# MainBoard_MCU.net
KiCad netlist of a schematic drawn in Altium Designer
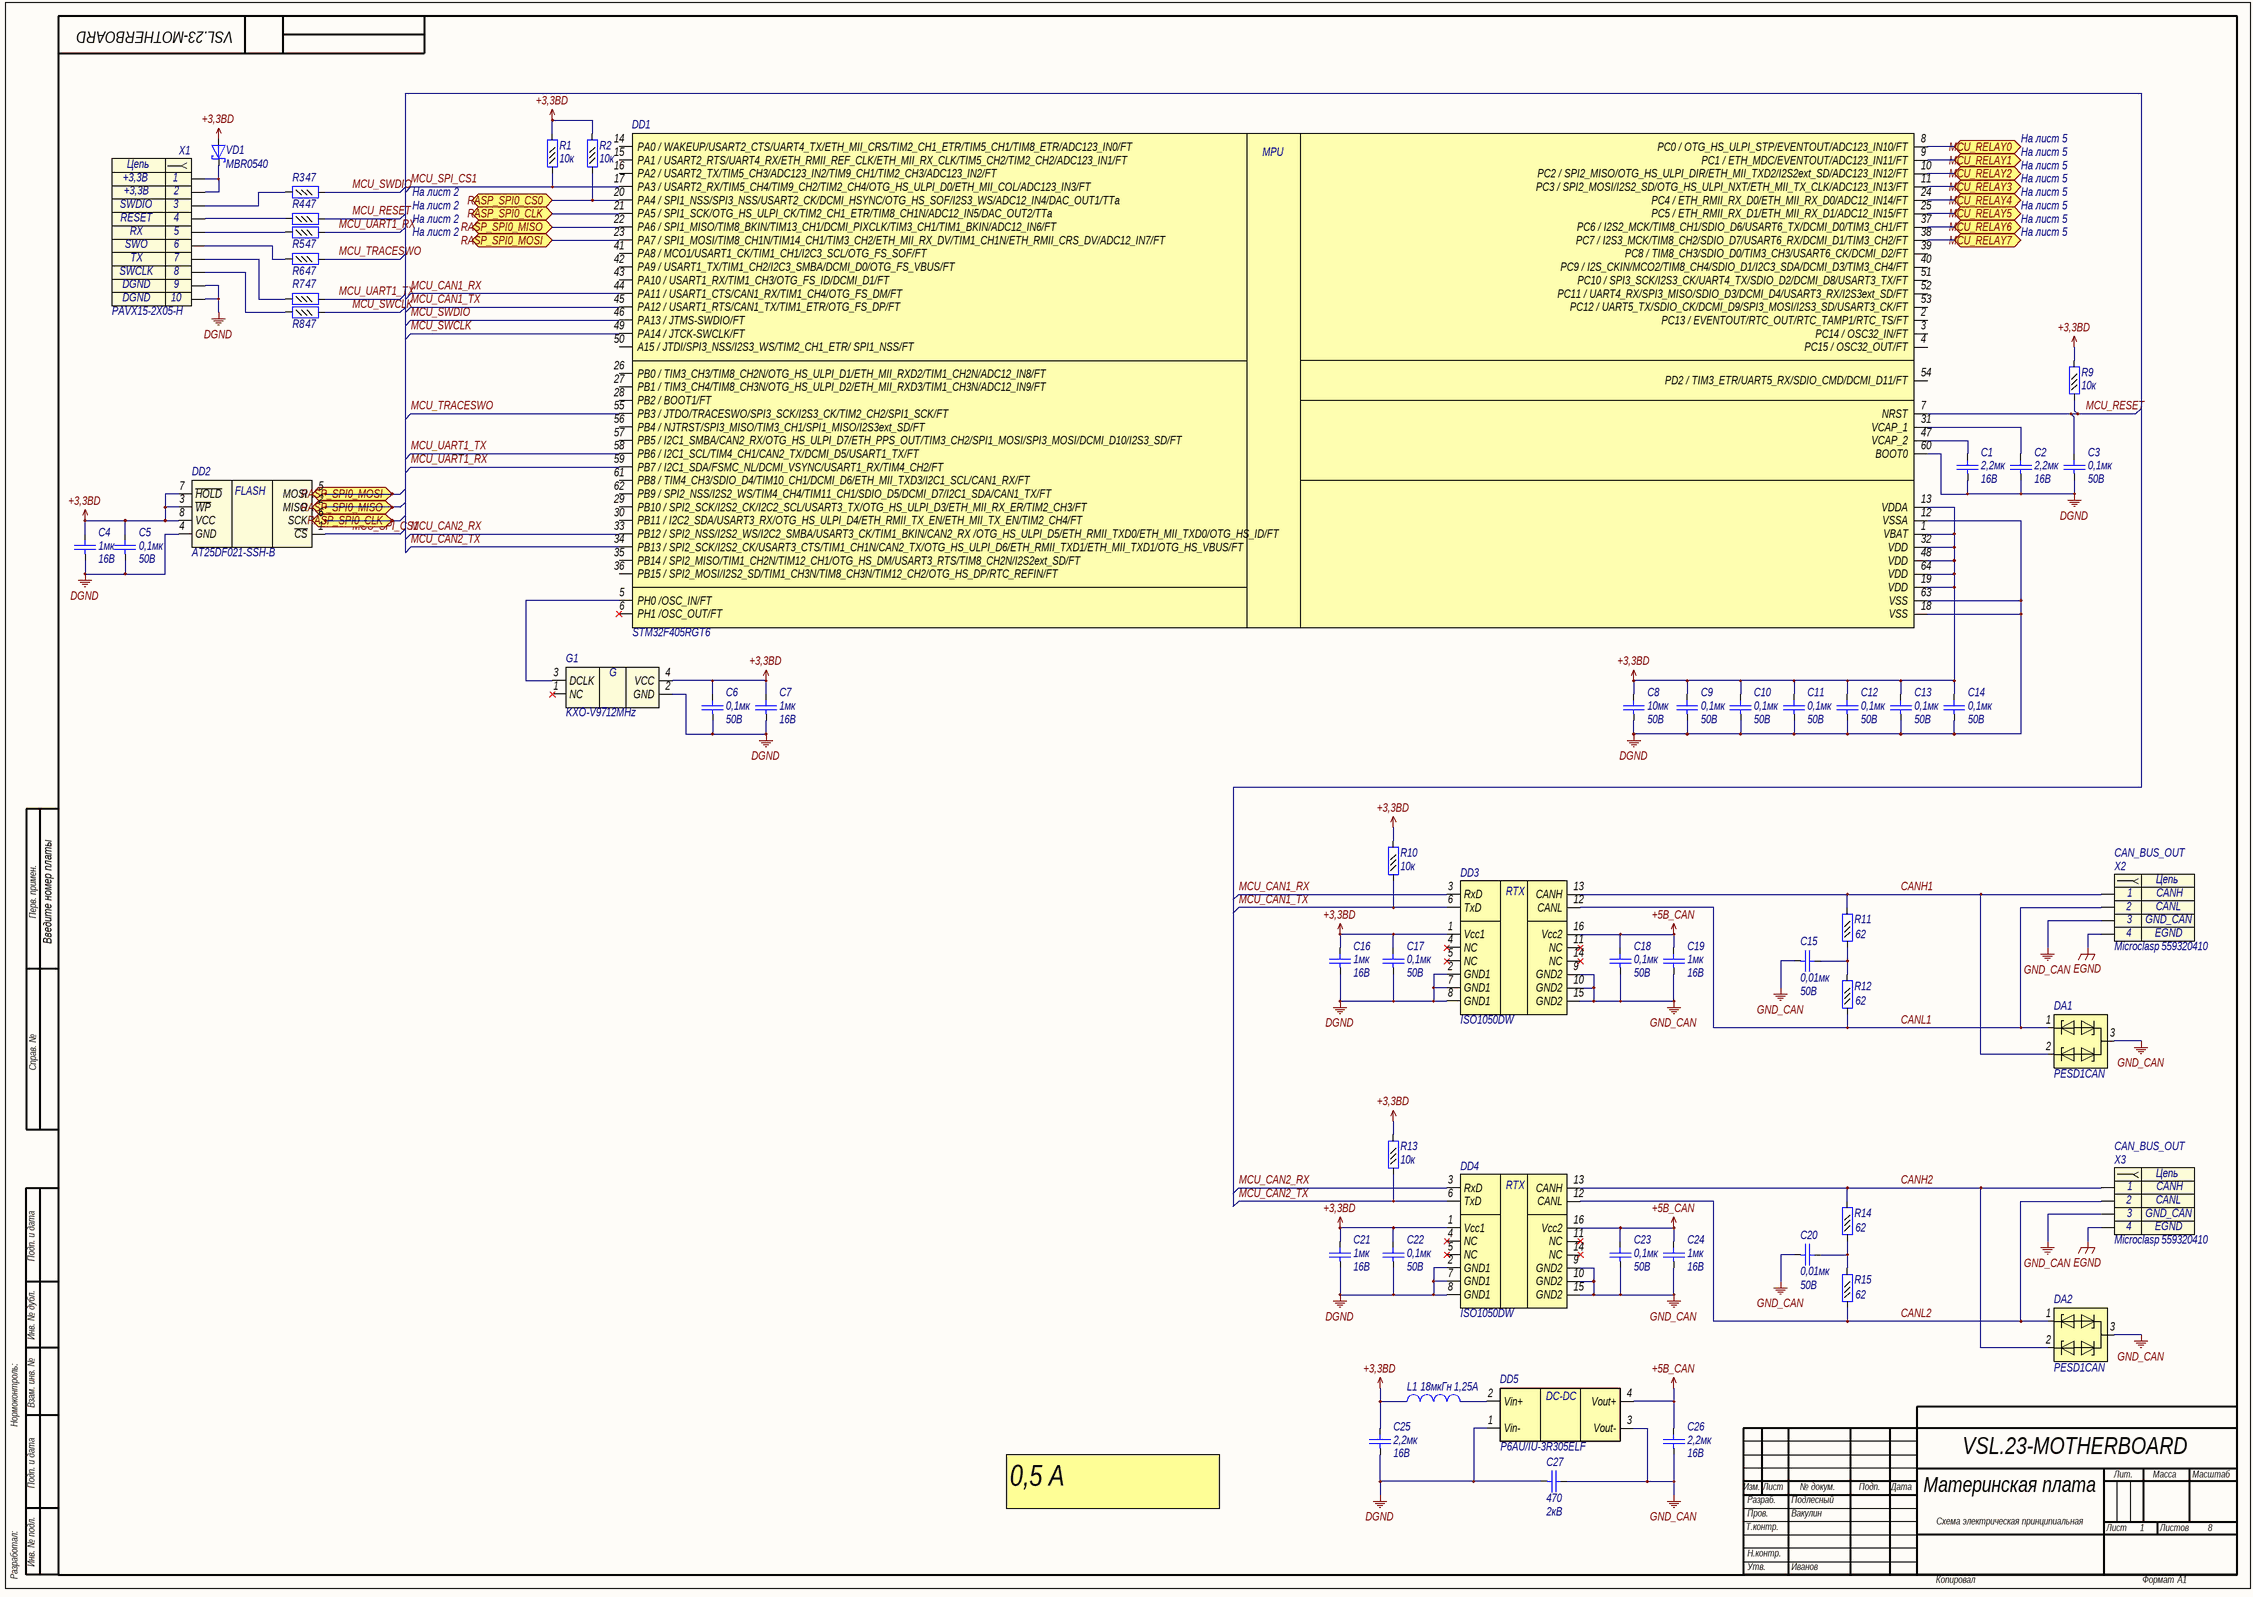
[diagram p0: MainBoard_MCU.SchDoc]

(export (version "E")
  (design (tool "Eeschema 10.0.6"))
  (components
    (comp (ref "C1")
      (value "2,2мк")
      (footprint "C0603")
      (description "Конденсатор")
      (fields (field (name "VOLTAGE") "16B") (field (name "PART NUMBER") "GRM188Z71C225ME43J"))
      (libsource (lib "MOP44") (part "Capacitor"))
    )
    (comp (ref "C2")
      (value "2,2мк")
      (footprint "C0603")
      (description "Конденсатор")
      (fields (field (name "VOLTAGE") "16B") (field (name "PART NUMBER") "GRM188Z71C225ME43J"))
      (libsource (lib "MOP44") (part "Capacitor"))
    )
    (comp (ref "C3")
      (value "0,1мк")
      (footprint "C0402")
      (description "Конденсатор")
      (fields
        (field (name "VOLTAGE") "50В")
        (field (name "PART NUMBER") "GRM155R71H104KE14D ")
        (field (name "Comment") "Capacitor")
      )
      (libsource (lib "MOP44") (part "Capacitor"))
    )
    (comp (ref "C4")
      (value "1мк")
      (footprint "C0603")
      (description "Конденсатор")
      (fields
        (field (name "VOLTAGE") "16B")
        (field (name "PART NUMBER") "GRM188R71C105KA12D**")
        (field (name "Comment") "Capacitor")
      )
      (libsource (lib "MOP44") (part "Capacitor"))
    )
    (comp (ref "C5")
      (value "0,1мк")
      (footprint "C0402")
      (description "Конденсатор")
      (fields
        (field (name "VOLTAGE") "50В")
        (field (name "PART NUMBER") "GRM155R71H104KE14D ")
        (field (name "Comment") "Capacitor")
      )
      (libsource (lib "MOP44") (part "Capacitor"))
    )
    (comp (ref "C6")
      (value "0,1мк")
      (footprint "C0402")
      (description "Конденсатор")
      (fields
        (field (name "VOLTAGE") "50В")
        (field (name "PART NUMBER") "GRM155R71H104KE14D ")
        (field (name "Comment") "Capacitor")
      )
      (libsource (lib "MOP44") (part "Capacitor"))
    )
    (comp (ref "C7")
      (value "1мк")
      (footprint "C0603")
      (description "Конденсатор")
      (fields
        (field (name "VOLTAGE") "16B")
        (field (name "PART NUMBER") "GRM188R71C105KA12D**")
        (field (name "Comment") "Capacitor")
      )
      (libsource (lib "MOP44") (part "Capacitor"))
    )
    (comp (ref "C8")
      (value "10мк")
      (footprint "C1210")
      (description "Конденсатор")
      (fields (field (name "VOLTAGE") "50В") (field (name "PART NUMBER") "C3225X7R1H106K250AC"))
      (libsource (lib "MOP44") (part "Capacitor"))
    )
    (comp (ref "C9")
      (value "0,1мк")
      (footprint "C0402")
      (description "Конденсатор")
      (fields
        (field (name "VOLTAGE") "50В")
        (field (name "PART NUMBER") "GRM155R71H104KE14D ")
        (field (name "Comment") "Capacitor")
      )
      (libsource (lib "MOP44") (part "Capacitor"))
    )
    (comp (ref "C10")
      (value "0,1мк")
      (footprint "C0402")
      (description "Конденсатор")
      (fields
        (field (name "VOLTAGE") "50В")
        (field (name "PART NUMBER") "GRM155R71H104KE14D ")
        (field (name "Comment") "Capacitor")
      )
      (libsource (lib "MOP44") (part "Capacitor"))
    )
    (comp (ref "C11")
      (value "0,1мк")
      (footprint "C0402")
      (description "Конденсатор")
      (fields
        (field (name "VOLTAGE") "50В")
        (field (name "PART NUMBER") "GRM155R71H104KE14D ")
        (field (name "Comment") "Capacitor")
      )
      (libsource (lib "MOP44") (part "Capacitor"))
    )
    (comp (ref "C12")
      (value "0,1мк")
      (footprint "C0402")
      (description "Конденсатор")
      (fields
        (field (name "VOLTAGE") "50В")
        (field (name "PART NUMBER") "GRM155R71H104KE14D ")
        (field (name "Comment") "Capacitor")
      )
      (libsource (lib "MOP44") (part "Capacitor"))
    )
    (comp (ref "C13")
      (value "0,1мк")
      (footprint "C0402")
      (description "Конденсатор")
      (fields
        (field (name "VOLTAGE") "50В")
        (field (name "PART NUMBER") "GRM155R71H104KE14D ")
        (field (name "Comment") "Capacitor")
      )
      (libsource (lib "MOP44") (part "Capacitor"))
    )
    (comp (ref "C14")
      (value "0,1мк")
      (footprint "C0402")
      (description "Конденсатор")
      (fields
        (field (name "VOLTAGE") "50В")
        (field (name "PART NUMBER") "GRM155R71H104KE14D ")
        (field (name "Comment") "Capacitor")
      )
      (libsource (lib "MOP44") (part "Capacitor"))
    )
    (comp (ref "C15")
      (value "0,01мк")
      (footprint "C0402")
      (description "Конденсатор")
      (fields
        (field (name "VOLTAGE") "50B")
        (field (name "PART NUMBER") "GRM155R71H103K")
        (field (name "Comment") "Capacitor")
      )
      (libsource (lib "MOP44") (part "Capacitor"))
    )
    (comp (ref "C16")
      (value "1мк")
      (footprint "C0603")
      (description "Конденсатор")
      (fields
        (field (name "VOLTAGE") "16B")
        (field (name "PART NUMBER") "GRM188R71C105KA12D**")
        (field (name "Comment") "Capacitor")
      )
      (libsource (lib "MOP44") (part "Capacitor"))
    )
    (comp (ref "C17")
      (value "0,1мк")
      (footprint "C0402")
      (description "Конденсатор")
      (fields
        (field (name "VOLTAGE") "50В")
        (field (name "PART NUMBER") "GRM155R71H104KE14D ")
        (field (name "Comment") "Capacitor")
      )
      (libsource (lib "MOP44") (part "Capacitor"))
    )
    (comp (ref "C18")
      (value "0,1мк")
      (footprint "C0402")
      (description "Конденсатор")
      (fields
        (field (name "VOLTAGE") "50В")
        (field (name "PART NUMBER") "GRM155R71H104KE14D ")
        (field (name "Comment") "Capacitor")
      )
      (libsource (lib "MOP44") (part "Capacitor"))
    )
    (comp (ref "C19")
      (value "1мк")
      (footprint "C0603")
      (description "Конденсатор")
      (fields
        (field (name "VOLTAGE") "16B")
        (field (name "PART NUMBER") "GRM188R71C105KA12D**")
        (field (name "Comment") "Capacitor")
      )
      (libsource (lib "MOP44") (part "Capacitor"))
    )
    (comp (ref "C20")
      (value "0,01мк")
      (footprint "C0402")
      (description "Конденсатор")
      (fields
        (field (name "VOLTAGE") "50B")
        (field (name "PART NUMBER") "GRM155R71H103K")
        (field (name "Comment") "Capacitor")
      )
      (libsource (lib "MOP44") (part "Capacitor"))
    )
    (comp (ref "C21")
      (value "1мк")
      (footprint "C0603")
      (description "Конденсатор")
      (fields
        (field (name "VOLTAGE") "16B")
        (field (name "PART NUMBER") "GRM188R71C105KA12D**")
        (field (name "Comment") "Capacitor")
      )
      (libsource (lib "MOP44") (part "Capacitor"))
    )
    (comp (ref "C22")
      (value "0,1мк")
      (footprint "C0402")
      (description "Конденсатор")
      (fields
        (field (name "VOLTAGE") "50В")
        (field (name "PART NUMBER") "GRM155R71H104KE14D ")
        (field (name "Comment") "Capacitor")
      )
      (libsource (lib "MOP44") (part "Capacitor"))
    )
    (comp (ref "C23")
      (value "0,1мк")
      (footprint "C0402")
      (description "Конденсатор")
      (fields
        (field (name "VOLTAGE") "50В")
        (field (name "PART NUMBER") "GRM155R71H104KE14D ")
        (field (name "Comment") "Capacitor")
      )
      (libsource (lib "MOP44") (part "Capacitor"))
    )
    (comp (ref "C24")
      (value "1мк")
      (footprint "C0603")
      (description "Конденсатор")
      (fields
        (field (name "VOLTAGE") "16B")
        (field (name "PART NUMBER") "GRM188R71C105KA12D**")
        (field (name "Comment") "Capacitor")
      )
      (libsource (lib "MOP44") (part "Capacitor"))
    )
    (comp (ref "C25")
      (value "2,2мк")
      (footprint "C0603")
      (description "Конденсатор")
      (fields (field (name "VOLTAGE") "16B") (field (name "PART NUMBER") "GRM188Z71C225ME43J"))
      (libsource (lib "MOP44") (part "Capacitor"))
    )
    (comp (ref "C26")
      (value "2,2мк")
      (footprint "C0603")
      (description "Конденсатор")
      (fields (field (name "VOLTAGE") "16B") (field (name "PART NUMBER") "GRM188Z71C225ME43J"))
      (libsource (lib "MOP44") (part "Capacitor"))
    )
    (comp (ref "C27")
      (value "470")
      (footprint "C1206")
      (description "Конденсатор")
      (fields
        (field (name "VOLTAGE") "2кВ")
        (field (name "PART NUMBER") "CC1206KKX7RDBB471 ")
        (field (name "Comment") "Capacitor")
      )
      (libsource (lib "MOP44") (part "Capacitor"))
    )
    (comp (ref "DA1")
      (value "PESD")
      (footprint "SOT23-3")
      (description "TVS")
      (fields (field (name "PART NUMBER") "PESD1CAN"))
      (libsource (lib "MOP44") (part "PESD"))
    )
    (comp (ref "DA2")
      (value "PESD")
      (footprint "SOT23-3")
      (description "TVS")
      (fields (field (name "PART NUMBER") "PESD1CAN"))
      (libsource (lib "MOP44") (part "PESD"))
    )
    (comp (ref "DD1")
      (value "STM32F405RGT6")
      (footprint "LQFP64")
      (libsource (lib "MOP44") (part "STM32F405RGT6"))
    )
    (comp (ref "DD2")
      (value "AT25DF021")
      (footprint "SO8")
      (description "SPI Serial Flash  Memory")
      (fields (field (name "MANUFACTURER") "Adesto") (field (name "PART NUMBER") "AT25DF021-SSH-B"))
      (libsource (lib "MOP44") (part "AT25DF021"))
    )
    (comp (ref "DD3")
      (value "~")
      (footprint "SO16")
      (description "Isolated CAN Transceiver")
      (fields (field (name "PART NUMBER") "ISO1050DW"))
      (libsource (lib "MOP44") (part "ISO1050DW"))
    )
    (comp (ref "DD4")
      (value "~")
      (footprint "SO16")
      (description "Isolated CAN Transceiver")
      (fields (field (name "PART NUMBER") "ISO1050DW"))
      (libsource (lib "MOP44") (part "ISO1050DW"))
    )
    (comp (ref "DD5")
      (value "P6AU-xxxxELF")
      (footprint "SIP4")
      (description "DC/DC преобразователь")
      (fields
        (field (name "PART NUMBER") "P6AU/IU-3R305ELF")
        (field (name "MANUFACTURER") "PEAK Electronics")
      )
      (libsource (lib "MOP44") (part "P6AU-xxxxELF"))
    )
    (comp (ref "G1")
      (value "KXO")
      (footprint "QSMD7x5.2x1.8")
      (description "Кварц. генер. 32.768 МГц (HCMOS/TTL)")
      (fields (field (name "FREQUENCE") "12MHz") (field (name "PART NUMBER") "KXO-V97"))
      (libsource (lib "MOP44") (part "KXO"))
    )
    (comp (ref "L1")
      (value "18мкГн")
      (footprint "SDR0604")
      (description "EMI Suppression Filter")
      (fields
        (field (name "RATED CURRENT") "1,25A")
        (field (name "PART NUMBER") "SDR0604- 180YL")
        (field (name "Comment") "Inductor")
      )
      (libsource (lib "MOP44") (part "Inductor"))
    )
    (comp (ref "R1")
      (value "10к")
      (footprint "R0402")
      (description "Резистор")
      (fields (field (name "PART NUMBER") "RC0402FR-0710KL") (field (name "POWER") "0,062Вт"))
      (libsource (lib "") (part "Resistor_0,062Вт_1"))
    )
    (comp (ref "R2")
      (value "10к")
      (footprint "R0402")
      (description "Резистор")
      (fields (field (name "PART NUMBER") "RC0402FR-0710KL") (field (name "POWER") "0,062Вт"))
      (libsource (lib "") (part "Resistor_0,062Вт_1"))
    )
    (comp (ref "R3")
      (value "47")
      (footprint "R0402")
      (description "Резистор")
      (fields (field (name "PART NUMBER") "RC0402FR-0747RL") (field (name "POWER") "0,062Вт"))
      (libsource (lib "MOP44") (part "Resistor_0,062Вт"))
    )
    (comp (ref "R4")
      (value "47")
      (footprint "R0402")
      (description "Резистор")
      (fields (field (name "PART NUMBER") "RC0402FR-0747RL") (field (name "POWER") "0,062Вт"))
      (libsource (lib "MOP44") (part "Resistor_0,062Вт"))
    )
    (comp (ref "R5")
      (value "47")
      (footprint "R0402")
      (description "Резистор")
      (fields (field (name "PART NUMBER") "RC0402FR-0747RL") (field (name "POWER") "0,062Вт"))
      (libsource (lib "MOP44") (part "Resistor_0,062Вт"))
    )
    (comp (ref "R6")
      (value "47")
      (footprint "R0402")
      (description "Резистор")
      (fields (field (name "PART NUMBER") "RC0402FR-0747RL") (field (name "POWER") "0,062Вт"))
      (libsource (lib "MOP44") (part "Resistor_0,062Вт"))
    )
    (comp (ref "R7")
      (value "47")
      (footprint "R0402")
      (description "Резистор")
      (fields (field (name "PART NUMBER") "RC0402FR-0747RL") (field (name "POWER") "0,062Вт"))
      (libsource (lib "MOP44") (part "Resistor_0,062Вт"))
    )
    (comp (ref "R8")
      (value "47")
      (footprint "R0402")
      (description "Резистор")
      (fields (field (name "PART NUMBER") "RC0402FR-0747RL") (field (name "POWER") "0,062Вт"))
      (libsource (lib "MOP44") (part "Resistor_0,062Вт"))
    )
    (comp (ref "R9")
      (value "10к")
      (footprint "R0402")
      (description "Резистор")
      (fields (field (name "PART NUMBER") "RC0402FR-0710KL") (field (name "POWER") "0,062Вт"))
      (libsource (lib "") (part "Resistor_0,062Вт_1"))
    )
    (comp (ref "R10")
      (value "10к")
      (footprint "R0402")
      (description "Резистор")
      (fields (field (name "PART NUMBER") "RC0402FR-0710KL") (field (name "POWER") "0,062Вт"))
      (libsource (lib "") (part "Resistor_0,062Вт_1"))
    )
    (comp (ref "R11")
      (value "62")
      (footprint "R0402")
      (description "Резистор")
      (fields (field (name "PART NUMBER") "RC0402FR-0762RL") (field (name "POWER") "0,062Вт"))
      (libsource (lib "") (part "Resistor_0,062Вт_1"))
    )
    (comp (ref "R12")
      (value "62")
      (footprint "R0402")
      (description "Резистор")
      (fields (field (name "PART NUMBER") "RC0402FR-0762RL") (field (name "POWER") "0,062Вт"))
      (libsource (lib "") (part "Resistor_0,062Вт_1"))
    )
    (comp (ref "R13")
      (value "10к")
      (footprint "R0402")
      (description "Резистор")
      (fields (field (name "PART NUMBER") "RC0402FR-0710KL") (field (name "POWER") "0,062Вт"))
      (libsource (lib "") (part "Resistor_0,062Вт_1"))
    )
    (comp (ref "R14")
      (value "62")
      (footprint "R0402")
      (description "Резистор")
      (fields (field (name "PART NUMBER") "RC0402FR-0762RL") (field (name "POWER") "0,062Вт"))
      (libsource (lib "") (part "Resistor_0,062Вт_1"))
    )
    (comp (ref "R15")
      (value "62")
      (footprint "R0402")
      (description "Резистор")
      (fields (field (name "PART NUMBER") "RC0402FR-0762RL") (field (name "POWER") "0,062Вт"))
      (libsource (lib "") (part "Resistor_0,062Вт_1"))
    )
    (comp (ref "VD1")
      (value "DiodeSchottky")
      (footprint "SOD-123")
      (description "Диод Шоттки")
      (fields (field (name "PART NUMBER") "MBR0540"))
      (libsource (lib "MOP44") (part "DiodeSchottky"))
    )
    (comp (ref "X1")
      (value "Header_10_sct")
      (footprint "PAVX15-2X05-H")
      (description "Разъем - 10 конт. розетка")
      (fields (field (name "PART NUMBER") "PAVX15-2X05-H"))
      (libsource (lib "MOP44") (part "Header_10_sct"))
    )
    (comp (ref "X2")
      (value "CAN_BUS_OUT")
      (footprint "MOLEX_559320410")
      (description "Разъем - 4 конт. розетка")
      (fields (field (name "PART NUMBER") "559320410"))
      (libsource (lib "MOP44") (part "Header_4_sct"))
    )
    (comp (ref "X3")
      (value "CAN_BUS_OUT")
      (footprint "MOLEX_559320410")
      (description "Разъем - 4 конт. розетка")
      (fields (field (name "PART NUMBER") "559320410"))
      (libsource (lib "MOP44") (part "Header_4_sct"))
    )
  )
  (nets
    (net (code "1") (name "+3,3BD") (class "Default")
      (node (ref "C10") (pin "2") (pinfunction "2_2") (pintype "passive"))
      (node (ref "C11") (pin "2") (pinfunction "2_2") (pintype "passive"))
      (node (ref "C12") (pin "2") (pinfunction "2_2") (pintype "passive"))
      (node (ref "C13") (pin "2") (pinfunction "2_2") (pintype "passive"))
      (node (ref "C14") (pin "2") (pinfunction "2_2") (pintype "passive"))
      (node (ref "C16") (pin "2") (pinfunction "2_2") (pintype "passive"))
      (node (ref "C17") (pin "2") (pinfunction "2_2") (pintype "passive"))
      (node (ref "C21") (pin "2") (pinfunction "2_2") (pintype "passive"))
      (node (ref "C22") (pin "2") (pinfunction "2_2") (pintype "passive"))
      (node (ref "C25") (pin "2") (pinfunction "2_2") (pintype "passive"))
      (node (ref "C4") (pin "2") (pinfunction "2_2") (pintype "passive"))
      (node (ref "C5") (pin "2") (pinfunction "2_2") (pintype "passive"))
      (node (ref "C6") (pin "2") (pinfunction "2_2") (pintype "passive"))
      (node (ref "C7") (pin "2") (pinfunction "2_2") (pintype "passive"))
      (node (ref "C8") (pin "2") (pinfunction "2_2") (pintype "passive"))
      (node (ref "C9") (pin "2") (pinfunction "2_2") (pintype "passive"))
      (node (ref "DD1") (pin "1") (pinfunction "VBAT_1") (pintype "passive"))
      (node (ref "DD1") (pin "13") (pinfunction "VDDA_13") (pintype "passive"))
      (node (ref "DD1") (pin "19") (pinfunction "VDD_19") (pintype "passive"))
      (node (ref "DD1") (pin "32") (pinfunction "VDD_32") (pintype "passive"))
      (node (ref "DD1") (pin "48") (pinfunction "VDD_48") (pintype "passive"))
      (node (ref "DD1") (pin "64") (pinfunction "VDD_64") (pintype "passive"))
      (node (ref "DD2") (pin "3") (pinfunction "~{WP}_3") (pintype "power_in"))
      (node (ref "DD2") (pin "7") (pinfunction "~{HOLD}_7") (pintype "power_in"))
      (node (ref "DD2") (pin "8") (pinfunction "VCC_8") (pintype "power_in"))
      (node (ref "DD3") (pin "1") (pinfunction "Vcc1_1") (pintype "passive"))
      (node (ref "DD4") (pin "1") (pinfunction "Vcc1_1") (pintype "passive"))
      (node (ref "G1") (pin "4") (pinfunction "VCC_4") (pintype "power_in"))
      (node (ref "L1") (pin "1") (pinfunction "1_1") (pintype "passive"))
      (node (ref "R1") (pin "2") (pinfunction "2_2") (pintype "passive"))
      (node (ref "R10") (pin "2") (pinfunction "2_2") (pintype "passive"))
      (node (ref "R13") (pin "2") (pinfunction "2_2") (pintype "passive"))
      (node (ref "R2") (pin "2") (pinfunction "2_2") (pintype "passive"))
      (node (ref "R9") (pin "2") (pinfunction "2_2") (pintype "passive"))
      (node (ref "VD1") (pin "2") (pinfunction "A_2") (pintype "passive"))
    )
    (net (code "2") (name "+5B_CAN") (class "Default")
      (node (ref "C18") (pin "2") (pinfunction "2_2") (pintype "passive"))
      (node (ref "C19") (pin "2") (pinfunction "2_2") (pintype "passive"))
      (node (ref "C23") (pin "2") (pinfunction "2_2") (pintype "passive"))
      (node (ref "C24") (pin "2") (pinfunction "2_2") (pintype "passive"))
      (node (ref "C26") (pin "2") (pinfunction "2_2") (pintype "passive"))
      (node (ref "DD3") (pin "16") (pinfunction "Vcc2_16") (pintype "passive"))
      (node (ref "DD4") (pin "16") (pinfunction "Vcc2_16") (pintype "passive"))
      (node (ref "DD5") (pin "4") (pinfunction "Vout+_4") (pintype "passive"))
    )
    (net (code "3") (name "/CANH1") (class "Default")
      (node (ref "DA1") (pin "2") (pinfunction "1_2") (pintype "passive"))
      (node (ref "DD3") (pin "13") (pinfunction "CANH_13") (pintype "passive"))
      (node (ref "R11") (pin "2") (pinfunction "2_2") (pintype "passive"))
      (node (ref "X2") (pin "1") (pinfunction "1_1") (pintype "passive"))
    )
    (net (code "4") (name "/CANH2") (class "Default")
      (node (ref "DA2") (pin "2") (pinfunction "1_2") (pintype "passive"))
      (node (ref "DD4") (pin "13") (pinfunction "CANH_13") (pintype "passive"))
      (node (ref "R14") (pin "2") (pinfunction "2_2") (pintype "passive"))
      (node (ref "X3") (pin "1") (pinfunction "1_1") (pintype "passive"))
    )
    (net (code "5") (name "/CANL1") (class "Default")
      (node (ref "DA1") (pin "1") (pintype "passive"))
      (node (ref "DD3") (pin "12") (pinfunction "CANL_12") (pintype "passive"))
      (node (ref "R12") (pin "1") (pinfunction "1_1") (pintype "passive"))
      (node (ref "X2") (pin "2") (pinfunction "2_2") (pintype "passive"))
    )
    (net (code "6") (name "/CANL2") (class "Default")
      (node (ref "DA2") (pin "1") (pintype "passive"))
      (node (ref "DD4") (pin "12") (pinfunction "CANL_12") (pintype "passive"))
      (node (ref "R15") (pin "1") (pinfunction "1_1") (pintype "passive"))
      (node (ref "X3") (pin "2") (pinfunction "2_2") (pintype "passive"))
    )
    (net (code "7") (name "/MCU_CAN1_RX") (class "Default")
      (node (ref "DD1") (pin "44") (pinfunction "PA11_/_USART1_CTS/CAN1_RX/TIM1_CH4/OTG_FS_DM/FT_44") (pintype "passive"))
      (node (ref "DD3") (pin "3") (pinfunction "RxD_3") (pintype "passive"))
    )
    (net (code "8") (name "/MCU_CAN1_TX") (class "Default")
      (node (ref "DD1") (pin "45") (pinfunction "PA12_/_USART1_RTS/CAN1_TX/TIM1_ETR/OTG_FS_DP/FT_45") (pintype "passive"))
      (node (ref "DD3") (pin "6") (pinfunction "TxD_6") (pintype "passive"))
      (node (ref "R10") (pin "1") (pinfunction "1_1") (pintype "passive"))
    )
    (net (code "9") (name "/MCU_CAN2_RX") (class "Default")
      (node (ref "DD1") (pin "33") (pinfunction "PB12_/_SPI2_NSS/I2S2_WS/I2C2_SMBA/USART3_CK/TIM1_BKIN/CAN2_RX_/OTG_HS_ULPI_D5/ETH_RMII_TXD0/ETH_MII_TXD0/OTG_HS_ID/FT_33") (pintype "passive"))
      (node (ref "DD4") (pin "3") (pinfunction "RxD_3") (pintype "passive"))
    )
    (net (code "10") (name "/MCU_CAN2_TX") (class "Default")
      (node (ref "DD1") (pin "34") (pinfunction "PB13_/_SPI2_SCK/I2S2_CK/USART3_CTS/TIM1_CH1N/CAN2_TX/OTG_HS_ULPI_D6/ETH_RMII_TXD1/ETH_MII_TXD1/OTG_HS_VBUS/FT_34") (pintype "passive"))
      (node (ref "DD4") (pin "6") (pinfunction "TxD_6") (pintype "passive"))
      (node (ref "R13") (pin "1") (pinfunction "1_1") (pintype "passive"))
    )
    (net (code "11") (name "/MCU_RELAY0") (class "Default")
      (node (ref "DD1") (pin "8") (pinfunction "PC0_/_OTG_HS_ULPI_STP/EVENTOUT/ADC123_IN10/FT_8") (pintype "passive"))
    )
    (net (code "12") (name "/MCU_RELAY1") (class "Default")
      (node (ref "DD1") (pin "9") (pinfunction "PC1_/_ETH_MDC/EVENTOUT/ADC123_IN11/FT_9") (pintype "passive"))
    )
    (net (code "13") (name "/MCU_RELAY2") (class "Default")
      (node (ref "DD1") (pin "10") (pinfunction "PC2_/_SPI2_MISO/OTG_HS_ULPI_DIR/ETH_MII_TXD2/I2S2ext_SD/ADC123_IN12/FT_10") (pintype "passive"))
    )
    (net (code "14") (name "/MCU_RELAY3") (class "Default")
      (node (ref "DD1") (pin "11") (pinfunction "PC3_/_SPI2_MOSI/I2S2_SD/OTG_HS_ULPI_NXT/ETH_MII_TX_CLK/ADC123_IN13/FT_11") (pintype "passive"))
    )
    (net (code "15") (name "/MCU_RELAY4") (class "Default")
      (node (ref "DD1") (pin "24") (pinfunction "PC4_/_ETH_RMII_RX_D0/ETH_MII_RX_D0/ADC12_IN14/FT_24") (pintype "passive"))
    )
    (net (code "16") (name "/MCU_RELAY5") (class "Default")
      (node (ref "DD1") (pin "25") (pinfunction "PC5_/_ETH_RMII_RX_D1/ETH_MII_RX_D1/ADC12_IN15/FT_25") (pintype "passive"))
    )
    (net (code "17") (name "/MCU_RELAY6") (class "Default")
      (node (ref "DD1") (pin "37") (pinfunction "PC6_/_I2S2_MCK/TIM8_CH1/SDIO_D6/USART6_TX/DCMI_D0/TIM3_CH1/FT_37") (pintype "passive"))
    )
    (net (code "18") (name "/MCU_RELAY7") (class "Default")
      (node (ref "DD1") (pin "38") (pinfunction "PC7_/_I2S3_MCK/TIM8_CH2/SDIO_D7/USART6_RX/DCMI_D1/TIM3_CH2/FT_38") (pintype "passive"))
    )
    (net (code "19") (name "/MCU_RESET") (class "Default")
      (node (ref "C3") (pin "2") (pinfunction "2_2") (pintype "passive"))
      (node (ref "DD1") (pin "7") (pinfunction "NRST_7") (pintype "passive"))
      (node (ref "R4") (pin "2") (pinfunction "2_2") (pintype "passive"))
      (node (ref "R9") (pin "1") (pinfunction "1_1") (pintype "passive"))
    )
    (net (code "20") (name "/MCU_SPI_CS1") (class "Default")
      (node (ref "DD1") (pin "17") (pinfunction "PA3_/_USART2_RX/TIM5_CH4/TIM9_CH2/TIM2_CH4/OTG_HS_ULPI_D0/ETH_MII_COL/ADC123_IN3/FT_17") (pintype "passive"))
      (node (ref "DD2") (pin "1") (pinfunction "~{CS}_1") (pintype "power_in"))
      (node (ref "R1") (pin "1") (pinfunction "1_1") (pintype "passive"))
    )
    (net (code "21") (name "/MCU_SWCLK") (class "Default")
      (node (ref "DD1") (pin "49") (pinfunction "PA14_/_JTCK-SWCLK/FT_49") (pintype "passive"))
      (node (ref "R8") (pin "2") (pinfunction "2_2") (pintype "passive"))
    )
    (net (code "22") (name "/MCU_SWDIO") (class "Default")
      (node (ref "DD1") (pin "46") (pinfunction "PA13_/_JTMS-SWDIO/FT_46") (pintype "passive"))
      (node (ref "R3") (pin "2") (pinfunction "2_2") (pintype "passive"))
    )
    (net (code "23") (name "/MCU_TRACESWO") (class "Default")
      (node (ref "DD1") (pin "55") (pinfunction "PB3_/_JTDO/TRACESWO/SPI3_SCK/I2S3_CK/TIM2_CH2/SPI1_SCK/FT_55") (pintype "passive"))
      (node (ref "R6") (pin "2") (pinfunction "2_2") (pintype "passive"))
    )
    (net (code "24") (name "/MCU_UART1_RX") (class "Default")
      (node (ref "DD1") (pin "59") (pinfunction "PB7_/_I2C1_SDA/FSMC_NL/DCMI_VSYNC/USART1_RX/TIM4_CH2/FT_59") (pintype "passive"))
      (node (ref "R5") (pin "2") (pinfunction "2_2") (pintype "passive"))
    )
    (net (code "25") (name "/MCU_UART1_TX") (class "Default")
      (node (ref "DD1") (pin "58") (pinfunction "PB6_/_I2C1_SCL/TIM4_CH1/CAN2_TX/DCMI_D5/USART1_TX/FT_58") (pintype "passive"))
      (node (ref "R7") (pin "2") (pinfunction "2_2") (pintype "passive"))
    )
    (net (code "26") (name "/RASP_SPI0_CLK") (class "Default")
      (node (ref "DD1") (pin "21") (pinfunction "PA5_/_SPI1_SCK/OTG_HS_ULPI_CK/TIM2_CH1_ETR/TIM8_CH1N/ADC12_IN5/DAC_OUT2/TTa_21") (pintype "passive"))
      (node (ref "DD2") (pin "6") (pinfunction "SCK_6") (pintype "power_in"))
    )
    (net (code "27") (name "/RASP_SPI0_CS0") (class "Default")
      (node (ref "DD1") (pin "20") (pinfunction "PA4_/_SPI1_NSS/SPI3_NSS/USART2_CK/DCMI_HSYNC/OTG_HS_SOF/I2S3_WS/ADC12_IN4/DAC_OUT1/TTa_20") (pintype "passive"))
      (node (ref "R2") (pin "1") (pinfunction "1_1") (pintype "passive"))
    )
    (net (code "28") (name "/RASP_SPI0_MISO") (class "Default")
      (node (ref "DD1") (pin "22") (pinfunction "PA6_/_SPI1_MISO/TIM8_BKIN/TIM13_CH1/DCMI_PIXCLK/TIM3_CH1/TIM1_BKIN/ADC12_IN6/FT_22") (pintype "passive"))
      (node (ref "DD2") (pin "2") (pinfunction "MISO_2") (pintype "power_in"))
    )
    (net (code "29") (name "/RASP_SPI0_MOSI") (class "Default")
      (node (ref "DD1") (pin "23") (pinfunction "PA7_/_SPI1_MOSI/TIM8_CH1N/TIM14_CH1/TIM3_CH2/ETH_MII_RX_DV/TIM1_CH1N/ETH_RMII_CRS_DV/ADC12_IN7/FT_23") (pintype "passive"))
      (node (ref "DD2") (pin "5") (pinfunction "MOSI_5") (pintype "power_in"))
    )
    (net (code "30") (name "DGND") (class "Default")
      (node (ref "C1") (pin "1") (pinfunction "1_1") (pintype "passive"))
      (node (ref "C10") (pin "1") (pinfunction "1_1") (pintype "passive"))
      (node (ref "C11") (pin "1") (pinfunction "1_1") (pintype "passive"))
      (node (ref "C12") (pin "1") (pinfunction "1_1") (pintype "passive"))
      (node (ref "C13") (pin "1") (pinfunction "1_1") (pintype "passive"))
      (node (ref "C14") (pin "1") (pinfunction "1_1") (pintype "passive"))
      (node (ref "C16") (pin "1") (pinfunction "1_1") (pintype "passive"))
      (node (ref "C17") (pin "1") (pinfunction "1_1") (pintype "passive"))
      (node (ref "C2") (pin "1") (pinfunction "1_1") (pintype "passive"))
      (node (ref "C21") (pin "1") (pinfunction "1_1") (pintype "passive"))
      (node (ref "C22") (pin "1") (pinfunction "1_1") (pintype "passive"))
      (node (ref "C25") (pin "1") (pinfunction "1_1") (pintype "passive"))
      (node (ref "C27") (pin "1") (pinfunction "1_1") (pintype "passive"))
      (node (ref "C3") (pin "1") (pinfunction "1_1") (pintype "passive"))
      (node (ref "C4") (pin "1") (pinfunction "1_1") (pintype "passive"))
      (node (ref "C5") (pin "1") (pinfunction "1_1") (pintype "passive"))
      (node (ref "C6") (pin "1") (pinfunction "1_1") (pintype "passive"))
      (node (ref "C7") (pin "1") (pinfunction "1_1") (pintype "passive"))
      (node (ref "C8") (pin "1") (pinfunction "1_1") (pintype "passive"))
      (node (ref "C9") (pin "1") (pinfunction "1_1") (pintype "passive"))
      (node (ref "DD1") (pin "12") (pinfunction "VSSA_12") (pintype "passive"))
      (node (ref "DD1") (pin "18") (pinfunction "VSS_18") (pintype "passive"))
      (node (ref "DD1") (pin "60") (pinfunction "BOOT0_60") (pintype "passive"))
      (node (ref "DD1") (pin "63") (pinfunction "VSS_63") (pintype "passive"))
      (node (ref "DD2") (pin "4") (pinfunction "GND_4") (pintype "power_in"))
      (node (ref "DD3") (pin "2") (pinfunction "GND1_2") (pintype "passive"))
      (node (ref "DD3") (pin "7") (pinfunction "GND1_7") (pintype "passive"))
      (node (ref "DD3") (pin "8") (pinfunction "GND1_8") (pintype "passive"))
      (node (ref "DD4") (pin "2") (pinfunction "GND1_2") (pintype "passive"))
      (node (ref "DD4") (pin "7") (pinfunction "GND1_7") (pintype "passive"))
      (node (ref "DD4") (pin "8") (pinfunction "GND1_8") (pintype "passive"))
      (node (ref "DD5") (pin "1") (pinfunction "Vin-_1") (pintype "passive"))
      (node (ref "G1") (pin "2") (pinfunction "GND_2") (pintype "power_in"))
      (node (ref "X1") (pin "10") (pinfunction "10_10") (pintype "passive"))
      (node (ref "X1") (pin "9") (pinfunction "9_9") (pintype "passive"))
    )
    (net (code "31") (name "EGND") (class "Default")
      (node (ref "X2") (pin "4") (pinfunction "4_4") (pintype "passive"))
      (node (ref "X3") (pin "4") (pinfunction "4_4") (pintype "passive"))
    )
    (net (code "32") (name "GND_CAN") (class "Default")
      (node (ref "C15") (pin "1") (pinfunction "1_1") (pintype "passive"))
      (node (ref "C18") (pin "1") (pinfunction "1_1") (pintype "passive"))
      (node (ref "C19") (pin "1") (pinfunction "1_1") (pintype "passive"))
      (node (ref "C20") (pin "1") (pinfunction "1_1") (pintype "passive"))
      (node (ref "C23") (pin "1") (pinfunction "1_1") (pintype "passive"))
      (node (ref "C24") (pin "1") (pinfunction "1_1") (pintype "passive"))
      (node (ref "C26") (pin "1") (pinfunction "1_1") (pintype "passive"))
      (node (ref "C27") (pin "2") (pinfunction "2_2") (pintype "passive"))
      (node (ref "DA1") (pin "3") (pintype "passive"))
      (node (ref "DA2") (pin "3") (pintype "passive"))
      (node (ref "DD3") (pin "10") (pinfunction "GND2_10") (pintype "passive"))
      (node (ref "DD3") (pin "15") (pinfunction "GND2_15") (pintype "passive"))
      (node (ref "DD3") (pin "9") (pinfunction "GND2_9") (pintype "passive"))
      (node (ref "DD4") (pin "10") (pinfunction "GND2_10") (pintype "passive"))
      (node (ref "DD4") (pin "15") (pinfunction "GND2_15") (pintype "passive"))
      (node (ref "DD4") (pin "9") (pinfunction "GND2_9") (pintype "passive"))
      (node (ref "DD5") (pin "3") (pinfunction "Vout-_3") (pintype "passive"))
      (node (ref "X2") (pin "3") (pinfunction "3_3") (pintype "passive"))
      (node (ref "X3") (pin "3") (pinfunction "3_3") (pintype "passive"))
    )
    (net (code "33") (name "Net-(C15-Pad2)") (class "Default")
      (node (ref "C15") (pin "2") (pinfunction "2_2") (pintype "passive"))
      (node (ref "R11") (pin "1") (pinfunction "1_1") (pintype "passive"))
      (node (ref "R12") (pin "2") (pinfunction "2_2") (pintype "passive"))
    )
    (net (code "34") (name "Net-(C20-Pad2)") (class "Default")
      (node (ref "C20") (pin "2") (pinfunction "2_2") (pintype "passive"))
      (node (ref "R14") (pin "1") (pinfunction "1_1") (pintype "passive"))
      (node (ref "R15") (pin "2") (pinfunction "2_2") (pintype "passive"))
    )
    (net (code "35") (name "Net-(DD1-PH0_{slash}OSC_IN{slash}FT)") (class "Default")
      (node (ref "DD1") (pin "5") (pinfunction "PH0_/OSC_IN/FT_5") (pintype "passive"))
      (node (ref "G1") (pin "3") (pinfunction "DCLK_3") (pintype "power_in"))
    )
    (net (code "36") (name "Net-(DD1-VCAP_1)") (class "Default")
      (node (ref "C2") (pin "2") (pinfunction "2_2") (pintype "passive"))
      (node (ref "DD1") (pin "31") (pinfunction "VCAP_1_31") (pintype "passive"))
    )
    (net (code "37") (name "Net-(DD1-VCAP_2)") (class "Default")
      (node (ref "C1") (pin "2") (pinfunction "2_2") (pintype "passive"))
      (node (ref "DD1") (pin "47") (pinfunction "VCAP_2_47") (pintype "passive"))
    )
    (net (code "38") (name "Net-(DD5-Vin+)") (class "Default")
      (node (ref "DD5") (pin "2") (pinfunction "Vin+_2") (pintype "passive"))
      (node (ref "L1") (pin "2") (pinfunction "2_2") (pintype "passive"))
    )
    (net (code "39") (name "Net-(R3-Pad1)") (class "Default")
      (node (ref "R3") (pin "1") (pinfunction "1_1") (pintype "passive"))
      (node (ref "X1") (pin "3") (pinfunction "3_3") (pintype "passive"))
    )
    (net (code "40") (name "Net-(R4-Pad1)") (class "Default")
      (node (ref "R4") (pin "1") (pinfunction "1_1") (pintype "passive"))
      (node (ref "X1") (pin "4") (pinfunction "4_4") (pintype "passive"))
    )
    (net (code "41") (name "Net-(R5-Pad1)") (class "Default")
      (node (ref "R5") (pin "1") (pinfunction "1_1") (pintype "passive"))
      (node (ref "X1") (pin "5") (pinfunction "5_5") (pintype "passive"))
    )
    (net (code "42") (name "Net-(R6-Pad1)") (class "Default")
      (node (ref "R6") (pin "1") (pinfunction "1_1") (pintype "passive"))
      (node (ref "X1") (pin "6") (pinfunction "6_6") (pintype "passive"))
    )
    (net (code "43") (name "Net-(R7-Pad1)") (class "Default")
      (node (ref "R7") (pin "1") (pinfunction "1_1") (pintype "passive"))
      (node (ref "X1") (pin "7") (pinfunction "7_7") (pintype "passive"))
    )
    (net (code "44") (name "Net-(R8-Pad1)") (class "Default")
      (node (ref "R8") (pin "1") (pinfunction "1_1") (pintype "passive"))
      (node (ref "X1") (pin "8") (pinfunction "8_8") (pintype "passive"))
    )
    (net (code "45") (name "Net-(VD1-K)") (class "Default")
      (node (ref "VD1") (pin "1") (pinfunction "K_1") (pintype "passive"))
      (node (ref "X1") (pin "1") (pinfunction "1_1") (pintype "passive"))
      (node (ref "X1") (pin "2") (pinfunction "2_2") (pintype "passive"))
    )
    (net (code "46") (name "unconnected-(DD1-A15_{slash}_JTDI{slash}SPI3_NSS{slash}I2S3_WS{slash}TIM2_CH1_ETR{slash}_SPI1_NSS{slash}FT-Pad50)") (class "Default")
      (node (ref "DD1") (pin "50") (pinfunction "A15_/_JTDI/SPI3_NSS/I2S3_WS/TIM2_CH1_ETR/_SPI1_NSS/FT_50") (pintype "passive"))
    )
    (net (code "47") (name "unconnected-(DD1-PA0_{slash}_WAKEUP{slash}USART2_CTS{slash}UART4_TX{slash}ETH_MII_CRS{slash}TIM2_CH1_ETR{slash}TIM5_CH1{slash}TIM8_ETR{slash}ADC123_IN0{slash}FT-Pad14)") (class "Default")
      (node (ref "DD1") (pin "14") (pinfunction "PA0_/_WAKEUP/USART2_CTS/UART4_TX/ETH_MII_CRS/TIM2_CH1_ETR/TIM5_CH1/TIM8_ETR/ADC123_IN0/FT_14") (pintype "passive"))
    )
    (net (code "48") (name "unconnected-(DD1-PA1_{slash}_USART2_RTS{slash}UART4_RX{slash}ETH_RMII_REF_CLK{slash}ETH_MII_RX_CLK{slash}TIM5_CH2{slash}TIM2_CH2{slash}ADC123_IN1{slash}FT-Pad15)") (class "Default")
      (node (ref "DD1") (pin "15") (pinfunction "PA1_/_USART2_RTS/UART4_RX/ETH_RMII_REF_CLK/ETH_MII_RX_CLK/TIM5_CH2/TIM2_CH2/ADC123_IN1/FT_15") (pintype "passive"))
    )
    (net (code "49") (name "unconnected-(DD1-PA2_{slash}_USART2_TX{slash}TIM5_CH3{slash}ADC123_IN2{slash}TIM9_CH1{slash}TIM2_CH3{slash}ADC123_IN2{slash}FT-Pad16)") (class "Default")
      (node (ref "DD1") (pin "16") (pinfunction "PA2_/_USART2_TX/TIM5_CH3/ADC123_IN2/TIM9_CH1/TIM2_CH3/ADC123_IN2/FT_16") (pintype "passive"))
    )
    (net (code "50") (name "unconnected-(DD1-PA8_{slash}_MCO1{slash}USART1_CK{slash}TIM1_CH1{slash}I2C3_SCL{slash}OTG_FS_SOF{slash}FT-Pad41)") (class "Default")
      (node (ref "DD1") (pin "41") (pinfunction "PA8_/_MCO1/USART1_CK/TIM1_CH1/I2C3_SCL/OTG_FS_SOF/FT_41") (pintype "passive"))
    )
    (net (code "51") (name "unconnected-(DD1-PA9_{slash}_USART1_TX{slash}TIM1_CH2{slash}I2C3_SMBA{slash}DCMI_D0{slash}OTG_FS_VBUS{slash}FT-Pad42)") (class "Default")
      (node (ref "DD1") (pin "42") (pinfunction "PA9_/_USART1_TX/TIM1_CH2/I2C3_SMBA/DCMI_D0/OTG_FS_VBUS/FT_42") (pintype "passive"))
    )
    (net (code "52") (name "unconnected-(DD1-PA10_{slash}_USART1_RX{slash}TIM1_CH3{slash}OTG_FS_ID{slash}DCMI_D1{slash}FT-Pad43)") (class "Default")
      (node (ref "DD1") (pin "43") (pinfunction "PA10_/_USART1_RX/TIM1_CH3/OTG_FS_ID/DCMI_D1/FT_43") (pintype "passive"))
    )
    (net (code "53") (name "unconnected-(DD1-PB0_{slash}_TIM3_CH3{slash}TIM8_CH2N{slash}OTG_HS_ULPI_D1{slash}ETH_MII_RXD2{slash}TIM1_CH2N{slash}ADC12_IN8{slash}FT-Pad26)") (class "Default")
      (node (ref "DD1") (pin "26") (pinfunction "PB0_/_TIM3_CH3/TIM8_CH2N/OTG_HS_ULPI_D1/ETH_MII_RXD2/TIM1_CH2N/ADC12_IN8/FT_26") (pintype "passive"))
    )
    (net (code "54") (name "unconnected-(DD1-PB1_{slash}_TIM3_CH4{slash}TIM8_CH3N{slash}OTG_HS_ULPI_D2{slash}ETH_MII_RXD3{slash}TIM1_CH3N{slash}ADC12_IN9{slash}FT-Pad27)") (class "Default")
      (node (ref "DD1") (pin "27") (pinfunction "PB1_/_TIM3_CH4/TIM8_CH3N/OTG_HS_ULPI_D2/ETH_MII_RXD3/TIM1_CH3N/ADC12_IN9/FT_27") (pintype "passive"))
    )
    (net (code "55") (name "unconnected-(DD1-PB2_{slash}_BOOT1{slash}FT-Pad28)") (class "Default")
      (node (ref "DD1") (pin "28") (pinfunction "PB2_/_BOOT1/FT_28") (pintype "passive"))
    )
    (net (code "56") (name "unconnected-(DD1-PB4_{slash}_NJTRST{slash}SPI3_MISO{slash}TIM3_CH1{slash}SPI1_MISO{slash}I2S3ext_SD{slash}FT-Pad56)") (class "Default")
      (node (ref "DD1") (pin "56") (pinfunction "PB4_/_NJTRST/SPI3_MISO/TIM3_CH1/SPI1_MISO/I2S3ext_SD/FT_56") (pintype "passive"))
    )
    (net (code "57") (name "unconnected-(DD1-PB5_{slash}_I2C1_SMBA{slash}CAN2_RX{slash}OTG_HS_ULPI_D7{slash}ETH_PPS_OUT{slash}TIM3_CH2{slash}SPI1_MOSI{slash}SPI3_MOSI{slash}DCMI_D10{slash}I2S3_SD{slash}FT-Pad57)") (class "Default")
      (node (ref "DD1") (pin "57") (pinfunction "PB5_/_I2C1_SMBA/CAN2_RX/OTG_HS_ULPI_D7/ETH_PPS_OUT/TIM3_CH2/SPI1_MOSI/SPI3_MOSI/DCMI_D10/I2S3_SD/FT_57") (pintype "passive"))
    )
    (net (code "58") (name "unconnected-(DD1-PB8_{slash}_TIM4_CH3{slash}SDIO_D4{slash}TIM10_CH1{slash}DCMI_D6{slash}ETH_MII_TXD3{slash}I2C1_SCL{slash}CAN1_RX{slash}FT-Pad61)") (class "Default")
      (node (ref "DD1") (pin "61") (pinfunction "PB8_/_TIM4_CH3/SDIO_D4/TIM10_CH1/DCMI_D6/ETH_MII_TXD3/I2C1_SCL/CAN1_RX/FT_61") (pintype "passive"))
    )
    (net (code "59") (name "unconnected-(DD1-PB9_{slash}_SPI2_NSS{slash}I2S2_WS{slash}TIM4_CH4{slash}TIM11_CH1{slash}SDIO_D5{slash}DCMI_D7{slash}I2C1_SDA{slash}CAN1_TX{slash}FT-Pad62)") (class "Default")
      (node (ref "DD1") (pin "62") (pinfunction "PB9_/_SPI2_NSS/I2S2_WS/TIM4_CH4/TIM11_CH1/SDIO_D5/DCMI_D7/I2C1_SDA/CAN1_TX/FT_62") (pintype "passive"))
    )
    (net (code "60") (name "unconnected-(DD1-PB10_{slash}_SPI2_SCK{slash}I2S2_CK{slash}I2C2_SCL{slash}USART3_TX{slash}OTG_HS_ULPI_D3{slash}ETH_MII_RX_ER{slash}TIM2_CH3{slash}FT-Pad29)") (class "Default")
      (node (ref "DD1") (pin "29") (pinfunction "PB10_/_SPI2_SCK/I2S2_CK/I2C2_SCL/USART3_TX/OTG_HS_ULPI_D3/ETH_MII_RX_ER/TIM2_CH3/FT_29") (pintype "passive"))
    )
    (net (code "61") (name "unconnected-(DD1-PB11_{slash}_I2C2_SDA{slash}USART3_RX{slash}OTG_HS_ULPI_D4{slash}ETH_RMII_TX_EN{slash}ETH_MII_TX_EN{slash}TIM2_CH4{slash}FT-Pad30)") (class "Default")
      (node (ref "DD1") (pin "30") (pinfunction "PB11_/_I2C2_SDA/USART3_RX/OTG_HS_ULPI_D4/ETH_RMII_TX_EN/ETH_MII_TX_EN/TIM2_CH4/FT_30") (pintype "passive"))
    )
    (net (code "62") (name "unconnected-(DD1-PB14_{slash}_SPI2_MISO{slash}TIM1_CH2N{slash}TIM12_CH1{slash}OTG_HS_DM{slash}USART3_RTS{slash}TIM8_CH2N{slash}I2S2ext_SD{slash}FT-Pad35)") (class "Default")
      (node (ref "DD1") (pin "35") (pinfunction "PB14_/_SPI2_MISO/TIM1_CH2N/TIM12_CH1/OTG_HS_DM/USART3_RTS/TIM8_CH2N/I2S2ext_SD/FT_35") (pintype "passive"))
    )
    (net (code "63") (name "unconnected-(DD1-PB15_{slash}_SPI2_MOSI{slash}I2S2_SD{slash}TIM1_CH3N{slash}TIM8_CH3N{slash}TIM12_CH2{slash}OTG_HS_DP{slash}RTC_REFIN{slash}FT-Pad36)") (class "Default")
      (node (ref "DD1") (pin "36") (pinfunction "PB15_/_SPI2_MOSI/I2S2_SD/TIM1_CH3N/TIM8_CH3N/TIM12_CH2/OTG_HS_DP/RTC_REFIN/FT_36") (pintype "passive"))
    )
    (net (code "64") (name "unconnected-(DD1-PC8_{slash}_TIM8_CH3{slash}SDIO_D0{slash}TIM3_CH3{slash}USART6_CK{slash}DCMI_D2{slash}FT-Pad39)") (class "Default")
      (node (ref "DD1") (pin "39") (pinfunction "PC8_/_TIM8_CH3/SDIO_D0/TIM3_CH3/USART6_CK/DCMI_D2/FT_39") (pintype "passive"))
    )
    (net (code "65") (name "unconnected-(DD1-PC9_{slash}_I2S_CKIN{slash}MCO2{slash}TIM8_CH4{slash}SDIO_D1{slash}I2C3_SDA{slash}DCMI_D3{slash}TIM3_CH4{slash}FT-Pad40)") (class "Default")
      (node (ref "DD1") (pin "40") (pinfunction "PC9_/_I2S_CKIN/MCO2/TIM8_CH4/SDIO_D1/I2C3_SDA/DCMI_D3/TIM3_CH4/FT_40") (pintype "passive"))
    )
    (net (code "66") (name "unconnected-(DD1-PC10_{slash}_SPI3_SCK{slash}I2S3_CK{slash}UART4_TX{slash}SDIO_D2{slash}DCMI_D8{slash}USART3_TX{slash}FT-Pad51)") (class "Default")
      (node (ref "DD1") (pin "51") (pinfunction "PC10_/_SPI3_SCK/I2S3_CK/UART4_TX/SDIO_D2/DCMI_D8/USART3_TX/FT_51") (pintype "passive"))
    )
    (net (code "67") (name "unconnected-(DD1-PC11_{slash}_UART4_RX{slash}SPI3_MISO{slash}SDIO_D3{slash}DCMI_D4{slash}USART3_RX{slash}I2S3ext_SD{slash}FT-Pad52)") (class "Default")
      (node (ref "DD1") (pin "52") (pinfunction "PC11_/_UART4_RX/SPI3_MISO/SDIO_D3/DCMI_D4/USART3_RX/I2S3ext_SD/FT_52") (pintype "passive"))
    )
    (net (code "68") (name "unconnected-(DD1-PC12_{slash}_UART5_TX{slash}SDIO_CK{slash}DCMI_D9{slash}SPI3_MOSI{slash}I2S3_SD{slash}USART3_CK{slash}FT-Pad53)") (class "Default")
      (node (ref "DD1") (pin "53") (pinfunction "PC12_/_UART5_TX/SDIO_CK/DCMI_D9/SPI3_MOSI/I2S3_SD/USART3_CK/FT_53") (pintype "passive"))
    )
    (net (code "69") (name "unconnected-(DD1-PC13_{slash}_EVENTOUT{slash}RTC_OUT{slash}RTC_TAMP1{slash}RTC_TS{slash}FT-Pad2)") (class "Default")
      (node (ref "DD1") (pin "2") (pinfunction "PC13_/_EVENTOUT/RTC_OUT/RTC_TAMP1/RTC_TS/FT_2") (pintype "passive"))
    )
    (net (code "70") (name "unconnected-(DD1-PC14_{slash}_OSC32_IN{slash}FT-Pad3)") (class "Default")
      (node (ref "DD1") (pin "3") (pinfunction "PC14_/_OSC32_IN/FT_3") (pintype "passive"))
    )
    (net (code "71") (name "unconnected-(DD1-PC15_{slash}_OSC32_OUT{slash}FT-Pad4)") (class "Default")
      (node (ref "DD1") (pin "4") (pinfunction "PC15_/_OSC32_OUT/FT_4") (pintype "passive"))
    )
    (net (code "72") (name "unconnected-(DD1-PD2_{slash}_TIM3_ETR{slash}UART5_RX{slash}SDIO_CMD{slash}DCMI_D11{slash}FT-Pad54)") (class "Default")
      (node (ref "DD1") (pin "54") (pinfunction "PD2_/_TIM3_ETR/UART5_RX/SDIO_CMD/DCMI_D11/FT_54") (pintype "passive"))
    )
    (net (code "73") (name "unconnected-(DD1-PH1_{slash}OSC_OUT{slash}FT-Pad6)") (class "Default")
      (node (ref "DD1") (pin "6") (pinfunction "PH1_/OSC_OUT/FT_6") (pintype "passive+no_connect"))
    )
    (net (code "74") (name "unconnected-(DD3-NC-Pad4)") (class "Default")
      (node (ref "DD3") (pin "4") (pinfunction "NC_4") (pintype "passive+no_connect"))
    )
    (net (code "75") (name "unconnected-(DD3-NC-Pad5)") (class "Default")
      (node (ref "DD3") (pin "5") (pinfunction "NC_5") (pintype "passive+no_connect"))
    )
    (net (code "76") (name "unconnected-(DD3-NC-Pad11)") (class "Default")
      (node (ref "DD3") (pin "11") (pinfunction "NC_11") (pintype "passive+no_connect"))
    )
    (net (code "77") (name "unconnected-(DD3-NC-Pad14)") (class "Default")
      (node (ref "DD3") (pin "14") (pinfunction "NC_14") (pintype "passive+no_connect"))
    )
    (net (code "78") (name "unconnected-(DD4-NC-Pad4)") (class "Default")
      (node (ref "DD4") (pin "4") (pinfunction "NC_4") (pintype "passive+no_connect"))
    )
    (net (code "79") (name "unconnected-(DD4-NC-Pad5)") (class "Default")
      (node (ref "DD4") (pin "5") (pinfunction "NC_5") (pintype "passive+no_connect"))
    )
    (net (code "80") (name "unconnected-(DD4-NC-Pad11)") (class "Default")
      (node (ref "DD4") (pin "11") (pinfunction "NC_11") (pintype "passive+no_connect"))
    )
    (net (code "81") (name "unconnected-(DD4-NC-Pad14)") (class "Default")
      (node (ref "DD4") (pin "14") (pinfunction "NC_14") (pintype "passive+no_connect"))
    )
    (net (code "82") (name "unconnected-(G1-NC-Pad1)") (class "Default")
      (node (ref "G1") (pin "1") (pinfunction "NC_1") (pintype "power_in+no_connect"))
    )
  )
)
